# Relay_Shield.net
KiCad netlist of a schematic drawn in EAGLE
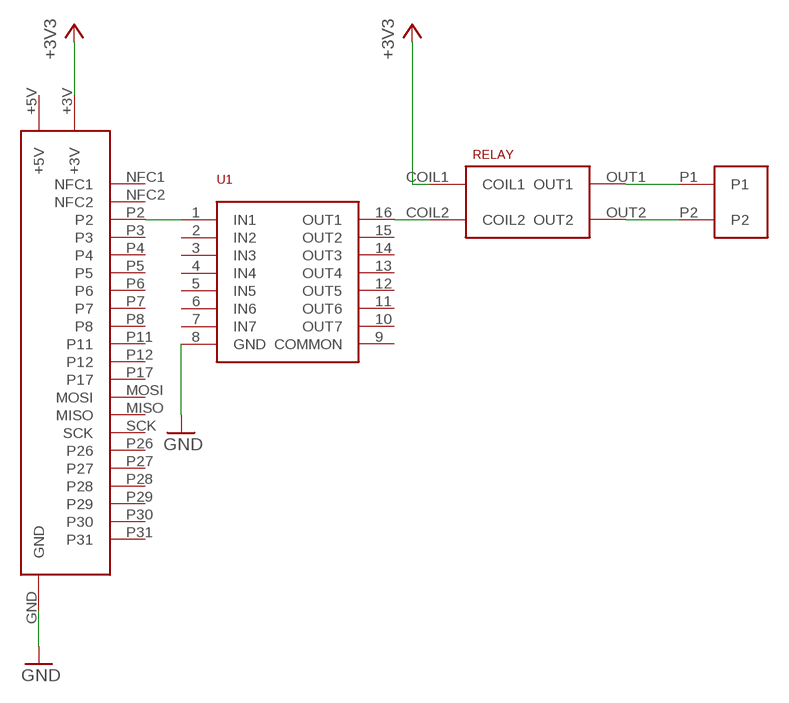
[diagram p0: schematic, sheet 1]

(export (version "E")
  (design (tool "Eeschema 10.0.6"))
  (components
    (comp (ref "RELAY")
      (value "3V_RELAY_OZ-SS-103LM1")
      (footprint "eagle-import:3V_RELAY_OZ-SS-103LM1")
      (libsource (lib "eagle-import") (part "3V_RELAY_OZ-SS-103LM1"))
    )
    (comp (ref "U$1")
      (value "EE02_SHIELD_HEADERSHIELD")
      (footprint "eagle-import:EE02_SHIELD_HEADER")
      (libsource (lib "eagle-import") (part "EE02_SHIELD_HEADERSHIELD"))
    )
    (comp (ref "U$2")
      (value "LOAD_TERMINAL_2P")
      (footprint "eagle-import:LOAD_CONNECTOR_2P")
      (libsource (lib "eagle-import") (part "LOAD_TERMINAL_2P"))
    )
    (comp (ref "U1")
      (value "ULN2003D1013TR")
      (footprint "eagle-import:SO16-NARROW")
      (libsource (lib "eagle-import") (part "ULN2003D1013TR"))
    )
  )
  (nets
    (net (code "1") (name "+3V3") (class "Default")
      (node (ref "RELAY") (pin "COIL1") (pinfunction "COIL1_COIL1") (pintype "bidirectional"))
      (node (ref "U$1") (pin "+3V") (pinfunction "+3V_+3V") (pintype "bidirectional"))
    )
    (net (code "2") (name "GND") (class "Default")
      (node (ref "U$1") (pin "GND") (pinfunction "GND_GND") (pintype "bidirectional"))
      (node (ref "U1") (pin "8") (pinfunction "GND_8") (pintype "bidirectional"))
    )
    (net (code "3") (name "Net-(RELAY-PadOUT1)") (class "Default")
      (node (ref "RELAY") (pin "OUT1") (pinfunction "OUT1_OUT1") (pintype "bidirectional"))
      (node (ref "U$2") (pin "P1") (pinfunction "P1_P1") (pintype "bidirectional"))
    )
    (net (code "4") (name "Net-(RELAY-PadOUT2)") (class "Default")
      (node (ref "RELAY") (pin "OUT2") (pinfunction "OUT2_OUT2") (pintype "bidirectional"))
      (node (ref "U$2") (pin "P2") (pinfunction "P2_P2") (pintype "bidirectional"))
    )
    (net (code "5") (name "Net-(U1-IN1)") (class "Default")
      (node (ref "U$1") (pin "P2") (pinfunction "P2_P2") (pintype "bidirectional"))
      (node (ref "U1") (pin "1") (pinfunction "IN1_1") (pintype "bidirectional"))
    )
    (net (code "6") (name "Net-(U1-OUT1)") (class "Default")
      (node (ref "RELAY") (pin "COIL2") (pinfunction "COIL2_COIL2") (pintype "bidirectional"))
      (node (ref "U1") (pin "16") (pinfunction "OUT1_16") (pintype "bidirectional"))
    )
    (net (code "7") (name "unconnected-(U$1-Pad+5V)") (class "Default")
      (node (ref "U$1") (pin "+5V") (pinfunction "+5V_+5V") (pintype "bidirectional"))
    )
    (net (code "8") (name "unconnected-(U$1-PadMISO)") (class "Default")
      (node (ref "U$1") (pin "MISO") (pinfunction "MISO_MISO") (pintype "bidirectional"))
    )
    (net (code "9") (name "unconnected-(U$1-PadMOSI)") (class "Default")
      (node (ref "U$1") (pin "MOSI") (pinfunction "MOSI_MOSI") (pintype "bidirectional"))
    )
    (net (code "10") (name "unconnected-(U$1-PadNFC1)") (class "Default")
      (node (ref "U$1") (pin "NFC1") (pinfunction "NFC1_NFC1") (pintype "bidirectional"))
    )
    (net (code "11") (name "unconnected-(U$1-PadNFC2)") (class "Default")
      (node (ref "U$1") (pin "NFC2") (pinfunction "NFC2_NFC2") (pintype "bidirectional"))
    )
    (net (code "12") (name "unconnected-(U$1-PadP3)") (class "Default")
      (node (ref "U$1") (pin "P3") (pinfunction "P3_P3") (pintype "bidirectional"))
    )
    (net (code "13") (name "unconnected-(U$1-PadP4)") (class "Default")
      (node (ref "U$1") (pin "P4") (pinfunction "P4_P4") (pintype "bidirectional"))
    )
    (net (code "14") (name "unconnected-(U$1-PadP5)") (class "Default")
      (node (ref "U$1") (pin "P5") (pinfunction "P5_P5") (pintype "bidirectional"))
    )
    (net (code "15") (name "unconnected-(U$1-PadP6)") (class "Default")
      (node (ref "U$1") (pin "P6") (pinfunction "P6_P6") (pintype "bidirectional"))
    )
    (net (code "16") (name "unconnected-(U$1-PadP7)") (class "Default")
      (node (ref "U$1") (pin "P7") (pinfunction "P7_P7") (pintype "bidirectional"))
    )
    (net (code "17") (name "unconnected-(U$1-PadP8)") (class "Default")
      (node (ref "U$1") (pin "P8") (pinfunction "P8_P8") (pintype "bidirectional"))
    )
    (net (code "18") (name "unconnected-(U$1-PadP11)") (class "Default")
      (node (ref "U$1") (pin "P11") (pinfunction "P11_P11") (pintype "bidirectional"))
    )
    (net (code "19") (name "unconnected-(U$1-PadP12)") (class "Default")
      (node (ref "U$1") (pin "P12") (pinfunction "P12_P12") (pintype "bidirectional"))
    )
    (net (code "20") (name "unconnected-(U$1-PadP17)") (class "Default")
      (node (ref "U$1") (pin "P17") (pinfunction "P17_P17") (pintype "bidirectional"))
    )
    (net (code "21") (name "unconnected-(U$1-PadP26)") (class "Default")
      (node (ref "U$1") (pin "P26") (pinfunction "P26_P26") (pintype "bidirectional"))
    )
    (net (code "22") (name "unconnected-(U$1-PadP27)") (class "Default")
      (node (ref "U$1") (pin "P27") (pinfunction "P27_P27") (pintype "bidirectional"))
    )
    (net (code "23") (name "unconnected-(U$1-PadP28)") (class "Default")
      (node (ref "U$1") (pin "P28") (pinfunction "P28_P28") (pintype "bidirectional"))
    )
    (net (code "24") (name "unconnected-(U$1-PadP29)") (class "Default")
      (node (ref "U$1") (pin "P29") (pinfunction "P29_P29") (pintype "bidirectional"))
    )
    (net (code "25") (name "unconnected-(U$1-PadP30)") (class "Default")
      (node (ref "U$1") (pin "P30") (pinfunction "P30_P30") (pintype "bidirectional"))
    )
    (net (code "26") (name "unconnected-(U$1-PadP31)") (class "Default")
      (node (ref "U$1") (pin "P31") (pinfunction "P31_P31") (pintype "bidirectional"))
    )
    (net (code "27") (name "unconnected-(U$1-PadSCK)") (class "Default")
      (node (ref "U$1") (pin "SCK") (pinfunction "SCK_SCK") (pintype "bidirectional"))
    )
    (net (code "28") (name "unconnected-(U1-COMMON-Pad9)") (class "Default")
      (node (ref "U1") (pin "9") (pinfunction "COMMON_9") (pintype "bidirectional"))
    )
    (net (code "29") (name "unconnected-(U1-IN2-Pad2)") (class "Default")
      (node (ref "U1") (pin "2") (pinfunction "IN2_2") (pintype "bidirectional"))
    )
    (net (code "30") (name "unconnected-(U1-IN3-Pad3)") (class "Default")
      (node (ref "U1") (pin "3") (pinfunction "IN3_3") (pintype "bidirectional"))
    )
    (net (code "31") (name "unconnected-(U1-IN4-Pad4)") (class "Default")
      (node (ref "U1") (pin "4") (pinfunction "IN4_4") (pintype "bidirectional"))
    )
    (net (code "32") (name "unconnected-(U1-IN5-Pad5)") (class "Default")
      (node (ref "U1") (pin "5") (pinfunction "IN5_5") (pintype "bidirectional"))
    )
    (net (code "33") (name "unconnected-(U1-IN6-Pad6)") (class "Default")
      (node (ref "U1") (pin "6") (pinfunction "IN6_6") (pintype "bidirectional"))
    )
    (net (code "34") (name "unconnected-(U1-IN7-Pad7)") (class "Default")
      (node (ref "U1") (pin "7") (pinfunction "IN7_7") (pintype "bidirectional"))
    )
    (net (code "35") (name "unconnected-(U1-OUT2-Pad15)") (class "Default")
      (node (ref "U1") (pin "15") (pinfunction "OUT2_15") (pintype "bidirectional"))
    )
    (net (code "36") (name "unconnected-(U1-OUT3-Pad14)") (class "Default")
      (node (ref "U1") (pin "14") (pinfunction "OUT3_14") (pintype "bidirectional"))
    )
    (net (code "37") (name "unconnected-(U1-OUT4-Pad13)") (class "Default")
      (node (ref "U1") (pin "13") (pinfunction "OUT4_13") (pintype "bidirectional"))
    )
    (net (code "38") (name "unconnected-(U1-OUT5-Pad12)") (class "Default")
      (node (ref "U1") (pin "12") (pinfunction "OUT5_12") (pintype "bidirectional"))
    )
    (net (code "39") (name "unconnected-(U1-OUT6-Pad11)") (class "Default")
      (node (ref "U1") (pin "11") (pinfunction "OUT6_11") (pintype "bidirectional"))
    )
    (net (code "40") (name "unconnected-(U1-OUT7-Pad10)") (class "Default")
      (node (ref "U1") (pin "10") (pinfunction "OUT7_10") (pintype "bidirectional"))
    )
  )
)
